# CM0_Controller_FreeScale.net
KiCad netlist of a schematic drawn in Altium Designer
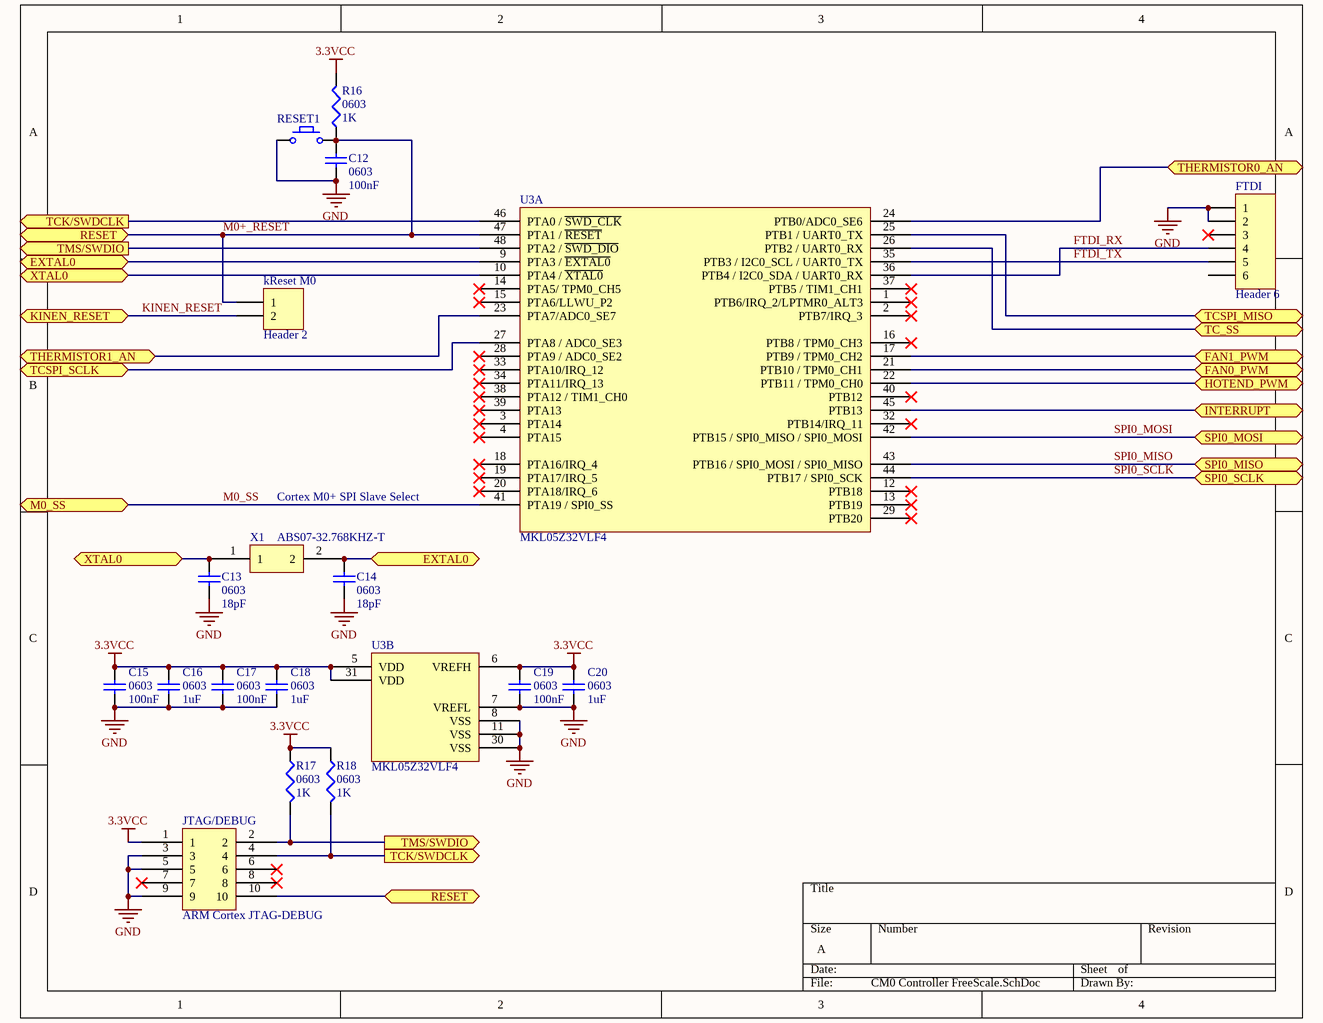
[diagram p0: CM0 Controller FreeScale.SchDoc]

(export (version "E")
  (design (tool "Eeschema 10.0.6"))
  (components
    (comp (ref "C12")
      (value "0603")
      (footprint "1608[0603]")
      (description "Capacitor (Semiconductor SIM Model)")
      (fields (field (name "ALTIUM_VALUE") "100nF") (field (name "PUBLISHER") "Altium Limited"))
      (libsource (lib "Miscellaneous Devices") (part "Cap Semi"))
    )
    (comp (ref "C13")
      (value "0603")
      (footprint "1608[0603]")
      (description "Capacitor (Semiconductor SIM Model)")
      (fields (field (name "ALTIUM_VALUE") "18pF") (field (name "PUBLISHER") "Altium Limited"))
      (libsource (lib "Miscellaneous Devices") (part "Cap Semi"))
    )
    (comp (ref "C14")
      (value "0603")
      (footprint "1608[0603]")
      (description "Capacitor (Semiconductor SIM Model)")
      (fields (field (name "ALTIUM_VALUE") "18pF") (field (name "PUBLISHER") "Altium Limited"))
      (libsource (lib "Miscellaneous Devices") (part "Cap Semi"))
    )
    (comp (ref "C15")
      (value "0603")
      (footprint "1608[0603]")
      (description "Capacitor (Semiconductor SIM Model)")
      (fields (field (name "ALTIUM_VALUE") "100nF") (field (name "PUBLISHER") "Altium Limited"))
      (libsource (lib "Miscellaneous Devices") (part "Cap Semi"))
    )
    (comp (ref "C16")
      (value "0603")
      (footprint "1608[0603]")
      (description "Capacitor (Semiconductor SIM Model)")
      (fields (field (name "ALTIUM_VALUE") "1uF") (field (name "PUBLISHER") "Altium Limited"))
      (libsource (lib "Miscellaneous Devices") (part "Cap Semi"))
    )
    (comp (ref "C17")
      (value "0603")
      (footprint "1608[0603]")
      (description "Capacitor (Semiconductor SIM Model)")
      (fields (field (name "ALTIUM_VALUE") "100nF") (field (name "PUBLISHER") "Altium Limited"))
      (libsource (lib "Miscellaneous Devices") (part "Cap Semi"))
    )
    (comp (ref "C18")
      (value "0603")
      (footprint "1608[0603]")
      (description "Capacitor (Semiconductor SIM Model)")
      (fields (field (name "ALTIUM_VALUE") "1uF") (field (name "PUBLISHER") "Altium Limited"))
      (libsource (lib "Miscellaneous Devices") (part "Cap Semi"))
    )
    (comp (ref "C19")
      (value "0603")
      (footprint "1608[0603]")
      (description "Capacitor (Semiconductor SIM Model)")
      (fields (field (name "ALTIUM_VALUE") "100nF") (field (name "PUBLISHER") "Altium Limited"))
      (libsource (lib "Miscellaneous Devices") (part "Cap Semi"))
    )
    (comp (ref "C20")
      (value "0603")
      (footprint "1608[0603]")
      (description "Capacitor (Semiconductor SIM Model)")
      (fields (field (name "ALTIUM_VALUE") "1uF") (field (name "PUBLISHER") "Altium Limited"))
      (libsource (lib "Miscellaneous Devices") (part "Cap Semi"))
    )
    (comp (ref "FTDI")
      (value "Header 6")
      (footprint "HDR1X6")
      (description "Header, 6-Pin")
      (fields (field (name "PUBLISHER") "Altium Limited"))
      (libsource (lib "Miscellaneous Connectors") (part "Header 6"))
    )
    (comp (ref "JTAG/DEBUG")
      (value "ARM Cortex JTAG-DEBUG")
      (footprint "FTSH-105-XX-X-DV")
      (libsource (lib "Adams Altium Library") (part "ARM Cortex JTAG-DEBUG Header"))
    )
    (comp (ref "kReset M0")
      (value "Header 2")
      (footprint "HDR1X2")
      (description "Header, 2-Pin")
      (fields (field (name "PUBLISHER") "Altium Limited"))
      (libsource (lib "Miscellaneous Connectors") (part "Header 2"))
    )
    (comp (ref "R16")
      (value "0603")
      (footprint "J1-0603")
      (description "Resistor")
      (fields (field (name "ALTIUM_VALUE") "1K") (field (name "PUBLISHER") "Altium Limited"))
      (libsource (lib "Miscellaneous Devices") (part "Res3"))
    )
    (comp (ref "R17")
      (value "0603")
      (footprint "J1-0603")
      (description "Resistor")
      (fields (field (name "ALTIUM_VALUE") "1K") (field (name "PUBLISHER") "Altium Limited"))
      (libsource (lib "Miscellaneous Devices") (part "Res3"))
    )
    (comp (ref "R18")
      (value "0603")
      (footprint "J1-0603")
      (description "Resistor")
      (fields (field (name "ALTIUM_VALUE") "1K") (field (name "PUBLISHER") "Altium Limited"))
      (libsource (lib "Miscellaneous Devices") (part "Res3"))
    )
    (comp (ref "RESET1")
      (value "Tactile Switch")
      (footprint "Mountain Switch TS6324T1607")
      (libsource (lib "Adams Altium Library") (part "Tactile Switch"))
    )
    (comp (ref "U3")
      (value "MKL05Z32VLF4")
      (footprint "MKL05Z32VLF4")
      (description "ARM Cortex M0+")
      (libsource (lib "ExtruderFinLib") (part "MKL05Z32VLF4"))
    )
    (comp (ref "X1")
      (value "ABS07-32.768KHZ-T")
      (footprint "ABS07-32.768KHZ-T")
      (description "ABS07-32.768KHZ-T RTC Crystal Oscillator")
      (libsource (lib "Adams Altium Library") (part "ABS07-32.768KHZ-T"))
    )
  )
  (nets
    (net (code "1") (name "/EXTAL0") (class "Default")
      (node (ref "C14") (pin "1") (pinfunction "1_1") (pintype "passive"))
      (node (ref "U3") (pin "9") (pinfunction "PTA3_/_~{EXTAL0}_9") (pintype "passive"))
      (node (ref "X1") (pin "2") (pinfunction "2_2") (pintype "passive"))
    )
    (net (code "2") (name "/FAN0_PWM") (class "Default")
      (node (ref "U3") (pin "21") (pinfunction "PTB10_/_TPM0_CH1_21") (pintype "passive"))
    )
    (net (code "3") (name "/FAN1_PWM") (class "Default")
      (node (ref "U3") (pin "17") (pinfunction "PTB9_/_TPM0_CH2_17") (pintype "passive"))
    )
    (net (code "4") (name "/FTDI_RX") (class "Default")
      (node (ref "FTDI") (pin "4") (pinfunction "4_4") (pintype "passive"))
      (node (ref "U3") (pin "36") (pinfunction "PTB4_/_I2C0_SDA_/_UART0_RX_36") (pintype "passive"))
    )
    (net (code "5") (name "/FTDI_TX") (class "Default")
      (node (ref "FTDI") (pin "5") (pinfunction "5_5") (pintype "passive"))
      (node (ref "U3") (pin "35") (pinfunction "PTB3_/_I2C0_SCL_/_UART0_TX_35") (pintype "passive"))
    )
    (net (code "6") (name "/HOTEND_PWM") (class "Default")
      (node (ref "U3") (pin "22") (pinfunction "PTB11_/_TPM0_CH0_22") (pintype "passive"))
    )
    (net (code "7") (name "/INTERRUPT") (class "Default")
      (node (ref "U3") (pin "45") (pinfunction "PTB13_45") (pintype "passive"))
    )
    (net (code "8") (name "/KINEN_RESET") (class "Default")
      (node (ref "kReset M0") (pin "2") (pinfunction "2_2") (pintype "passive"))
    )
    (net (code "9") (name "/M0+_RESET") (class "Default")
      (node (ref "C12") (pin "1") (pinfunction "1_1") (pintype "passive"))
      (node (ref "JTAG/DEBUG") (pin "10") (pinfunction "10_10") (pintype "passive"))
      (node (ref "R16") (pin "1") (pinfunction "1_1") (pintype "passive"))
      (node (ref "RESET1") (pin "2") (pintype "passive"))
      (node (ref "U3") (pin "47") (pinfunction "PTA1_/_~{RESET}_47") (pintype "passive"))
      (node (ref "kReset M0") (pin "1") (pinfunction "1_1") (pintype "passive"))
    )
    (net (code "10") (name "/M0_SS") (class "Default")
      (node (ref "U3") (pin "41") (pinfunction "PTA19_/_SPI0_SS_41") (pintype "passive"))
    )
    (net (code "11") (name "/SPI0_MISO") (class "Default")
      (node (ref "U3") (pin "43") (pinfunction "PTB16_/_SPI0_MOSI_43") (pintype "passive"))
    )
    (net (code "12") (name "/SPI0_MOSI") (class "Default")
      (node (ref "U3") (pin "42") (pinfunction "PTB15_/_SPI0_MISO_42") (pintype "passive"))
    )
    (net (code "13") (name "/SPI0_SCLK") (class "Default")
      (node (ref "U3") (pin "44") (pinfunction "PTB17_/_SPI0_SCK_44") (pintype "passive"))
    )
    (net (code "14") (name "/TCK{slash}SWDCLK") (class "Default")
      (node (ref "JTAG/DEBUG") (pin "4") (pinfunction "4_4") (pintype "passive"))
      (node (ref "R18") (pin "2") (pinfunction "2_2") (pintype "passive"))
      (node (ref "U3") (pin "46") (pinfunction "PTA0_/_~{SWD_CLK}_46") (pintype "passive"))
    )
    (net (code "15") (name "/TCSPI_MISO") (class "Default")
      (node (ref "U3") (pin "25") (pinfunction "PTB1_/_UART0_TX_25") (pintype "passive"))
    )
    (net (code "16") (name "/TCSPI_SCLK") (class "Default")
      (node (ref "U3") (pin "27") (pinfunction "PTA8_/_ADC0_SE3_27") (pintype "passive"))
    )
    (net (code "17") (name "/TC_SS") (class "Default")
      (node (ref "U3") (pin "26") (pinfunction "PTB2_/_UART0_RX_26") (pintype "passive"))
    )
    (net (code "18") (name "/THERMISTOR0_AN") (class "Default")
      (node (ref "U3") (pin "24") (pinfunction "PTB0/IRQ_8/LLWU_P4_24") (pintype "passive"))
    )
    (net (code "19") (name "/THERMISTOR1_AN") (class "Default")
      (node (ref "U3") (pin "23") (pinfunction "PTA7/IRQ_7/LLWU_P3_23") (pintype "passive"))
    )
    (net (code "20") (name "/TMS{slash}SWDIO") (class "Default")
      (node (ref "JTAG/DEBUG") (pin "2") (pinfunction "2_2") (pintype "passive"))
      (node (ref "R17") (pin "2") (pinfunction "2_2") (pintype "passive"))
      (node (ref "U3") (pin "48") (pinfunction "PTA2_/_~{SWD_DIO}_48") (pintype "passive"))
    )
    (net (code "21") (name "/XTAL0") (class "Default")
      (node (ref "C13") (pin "1") (pinfunction "1_1") (pintype "passive"))
      (node (ref "U3") (pin "10") (pinfunction "PTA4_/_~{XTAL0}_10") (pintype "passive"))
      (node (ref "X1") (pin "1") (pinfunction "1_1") (pintype "passive"))
    )
    (net (code "22") (name "3.3VCC") (class "Default")
      (node (ref "C15") (pin "2") (pinfunction "2_2") (pintype "passive"))
      (node (ref "C16") (pin "2") (pinfunction "2_2") (pintype "passive"))
      (node (ref "C17") (pin "2") (pinfunction "2_2") (pintype "passive"))
      (node (ref "C18") (pin "2") (pinfunction "2_2") (pintype "passive"))
      (node (ref "C19") (pin "1") (pinfunction "1_1") (pintype "passive"))
      (node (ref "C20") (pin "1") (pinfunction "1_1") (pintype "passive"))
      (node (ref "JTAG/DEBUG") (pin "1") (pinfunction "1_1") (pintype "passive"))
      (node (ref "R16") (pin "2") (pinfunction "2_2") (pintype "passive"))
      (node (ref "R17") (pin "1") (pinfunction "1_1") (pintype "passive"))
      (node (ref "R18") (pin "1") (pinfunction "1_1") (pintype "passive"))
      (node (ref "U3") (pin "31") (pinfunction "VDD_31") (pintype "passive"))
      (node (ref "U3") (pin "5") (pinfunction "VDD_5") (pintype "passive"))
      (node (ref "U3") (pin "6") (pinfunction "VREFH_6") (pintype "passive"))
    )
    (net (code "23") (name "GND") (class "Default")
      (node (ref "C12") (pin "2") (pinfunction "2_2") (pintype "passive"))
      (node (ref "C13") (pin "2") (pinfunction "2_2") (pintype "passive"))
      (node (ref "C14") (pin "2") (pinfunction "2_2") (pintype "passive"))
      (node (ref "C15") (pin "1") (pinfunction "1_1") (pintype "passive"))
      (node (ref "C16") (pin "1") (pinfunction "1_1") (pintype "passive"))
      (node (ref "C17") (pin "1") (pinfunction "1_1") (pintype "passive"))
      (node (ref "C18") (pin "1") (pinfunction "1_1") (pintype "passive"))
      (node (ref "C19") (pin "2") (pinfunction "2_2") (pintype "passive"))
      (node (ref "C20") (pin "2") (pinfunction "2_2") (pintype "passive"))
      (node (ref "FTDI") (pin "1") (pinfunction "1_1") (pintype "passive"))
      (node (ref "FTDI") (pin "2") (pinfunction "2_2") (pintype "passive"))
      (node (ref "JTAG/DEBUG") (pin "3") (pinfunction "3_3") (pintype "passive"))
      (node (ref "JTAG/DEBUG") (pin "5") (pinfunction "5_5") (pintype "passive"))
      (node (ref "JTAG/DEBUG") (pin "9") (pinfunction "9_9") (pintype "passive"))
      (node (ref "RESET1") (pin "1") (pintype "passive"))
      (node (ref "U3") (pin "11") (pinfunction "VSS_11") (pintype "passive"))
      (node (ref "U3") (pin "30") (pinfunction "VSS_30") (pintype "passive"))
      (node (ref "U3") (pin "7") (pinfunction "VREFL_7") (pintype "passive"))
      (node (ref "U3") (pin "8") (pinfunction "VSS_8") (pintype "passive"))
    )
    (net (code "24") (name "unconnected-(FTDI-Pad3)") (class "Default")
      (node (ref "FTDI") (pin "3") (pinfunction "3_3") (pintype "passive+no_connect"))
    )
    (net (code "25") (name "unconnected-(FTDI-Pad6)") (class "Default")
      (node (ref "FTDI") (pin "6") (pinfunction "6_6") (pintype "passive"))
    )
    (net (code "26") (name "unconnected-(JTAG/DEBUG-Pad6)") (class "Default")
      (node (ref "JTAG/DEBUG") (pin "6") (pinfunction "6_6") (pintype "passive+no_connect"))
    )
    (net (code "27") (name "unconnected-(JTAG/DEBUG-Pad7)") (class "Default")
      (node (ref "JTAG/DEBUG") (pin "7") (pinfunction "7_7") (pintype "passive+no_connect"))
    )
    (net (code "28") (name "unconnected-(JTAG/DEBUG-Pad8)") (class "Default")
      (node (ref "JTAG/DEBUG") (pin "8") (pinfunction "8_8") (pintype "passive+no_connect"))
    )
    (net (code "29") (name "unconnected-(U3A-PTA5{slash}LLWU_P{slash}RTC_CLK_IN-Pad14)") (class "Default")
      (node (ref "U3") (pin "14") (pinfunction "PTA5/LLWU_P/RTC_CLK_IN_14") (pintype "passive+no_connect"))
    )
    (net (code "30") (name "unconnected-(U3A-PTA6{slash}LLWU_P2-Pad15)") (class "Default")
      (node (ref "U3") (pin "15") (pinfunction "PTA6/LLWU_P2_15") (pintype "passive+no_connect"))
    )
    (net (code "31") (name "unconnected-(U3A-PTA9_{slash}_ADC0_SE2-Pad28)") (class "Default")
      (node (ref "U3") (pin "28") (pinfunction "PTA9_/_ADC0_SE2_28") (pintype "passive+no_connect"))
    )
    (net (code "32") (name "unconnected-(U3A-PTA10{slash}IRQ_12-Pad33)") (class "Default")
      (node (ref "U3") (pin "33") (pinfunction "PTA10/IRQ_12_33") (pintype "passive+no_connect"))
    )
    (net (code "33") (name "unconnected-(U3A-PTA11{slash}IRQ_13-Pad34)") (class "Default")
      (node (ref "U3") (pin "34") (pinfunction "PTA11/IRQ_13_34") (pintype "passive+no_connect"))
    )
    (net (code "34") (name "unconnected-(U3A-PTA12_{slash}_TIM1_CH0-Pad38)") (class "Default")
      (node (ref "U3") (pin "38") (pinfunction "PTA12_/_TIM1_CH0_38") (pintype "passive+no_connect"))
    )
    (net (code "35") (name "unconnected-(U3A-PTA13-Pad39)") (class "Default")
      (node (ref "U3") (pin "39") (pinfunction "PTA13_39") (pintype "passive+no_connect"))
    )
    (net (code "36") (name "unconnected-(U3A-PTA14-Pad3)") (class "Default")
      (node (ref "U3") (pin "3") (pinfunction "PTA14_3") (pintype "passive+no_connect"))
    )
    (net (code "37") (name "unconnected-(U3A-PTA15-Pad4)") (class "Default")
      (node (ref "U3") (pin "4") (pinfunction "PTA15_4") (pintype "passive+no_connect"))
    )
    (net (code "38") (name "unconnected-(U3A-PTA16{slash}IRQ_4-Pad18)") (class "Default")
      (node (ref "U3") (pin "18") (pinfunction "PTA16/IRQ_4_18") (pintype "passive+no_connect"))
    )
    (net (code "39") (name "unconnected-(U3A-PTA17{slash}IRQ_5-Pad19)") (class "Default")
      (node (ref "U3") (pin "19") (pinfunction "PTA17/IRQ_5_19") (pintype "passive+no_connect"))
    )
    (net (code "40") (name "unconnected-(U3A-PTA18{slash}IRQ_6-Pad20)") (class "Default")
      (node (ref "U3") (pin "20") (pinfunction "PTA18/IRQ_6_20") (pintype "passive+no_connect"))
    )
    (net (code "41") (name "unconnected-(U3A-PTB5_{slash}_TIM1_CH1-Pad37)") (class "Default")
      (node (ref "U3") (pin "37") (pinfunction "PTB5_/_TIM1_CH1_37") (pintype "passive+no_connect"))
    )
    (net (code "42") (name "unconnected-(U3A-PTB6{slash}IRQ_2{slash}LPTMR0_ALT3-Pad1)") (class "Default")
      (node (ref "U3") (pin "1") (pinfunction "PTB6/IRQ_2/LPTMR0_ALT3_1") (pintype "passive+no_connect"))
    )
    (net (code "43") (name "unconnected-(U3A-PTB7{slash}IRQ_3-Pad2)") (class "Default")
      (node (ref "U3") (pin "2") (pinfunction "PTB7/IRQ_3_2") (pintype "passive+no_connect"))
    )
    (net (code "44") (name "unconnected-(U3A-PTB8_{slash}_TPM0_CH3-Pad16)") (class "Default")
      (node (ref "U3") (pin "16") (pinfunction "PTB8_/_TPM0_CH3_16") (pintype "passive+no_connect"))
    )
    (net (code "45") (name "unconnected-(U3A-PTB12-Pad40)") (class "Default")
      (node (ref "U3") (pin "40") (pinfunction "PTB12_40") (pintype "passive+no_connect"))
    )
    (net (code "46") (name "unconnected-(U3A-PTB14{slash}IRQ_11-Pad32)") (class "Default")
      (node (ref "U3") (pin "32") (pinfunction "PTB14/IRQ_11_32") (pintype "passive+no_connect"))
    )
    (net (code "47") (name "unconnected-(U3A-PTB18-Pad12)") (class "Default")
      (node (ref "U3") (pin "12") (pinfunction "PTB18_12") (pintype "passive+no_connect"))
    )
    (net (code "48") (name "unconnected-(U3A-PTB19-Pad13)") (class "Default")
      (node (ref "U3") (pin "13") (pinfunction "PTB19_13") (pintype "passive+no_connect"))
    )
    (net (code "49") (name "unconnected-(U3A-PTB20-Pad29)") (class "Default")
      (node (ref "U3") (pin "29") (pinfunction "PTB20_29") (pintype "passive+no_connect"))
    )
  )
)
